# BT840_Temp.net
KiCad netlist of a schematic drawn in Altium Designer
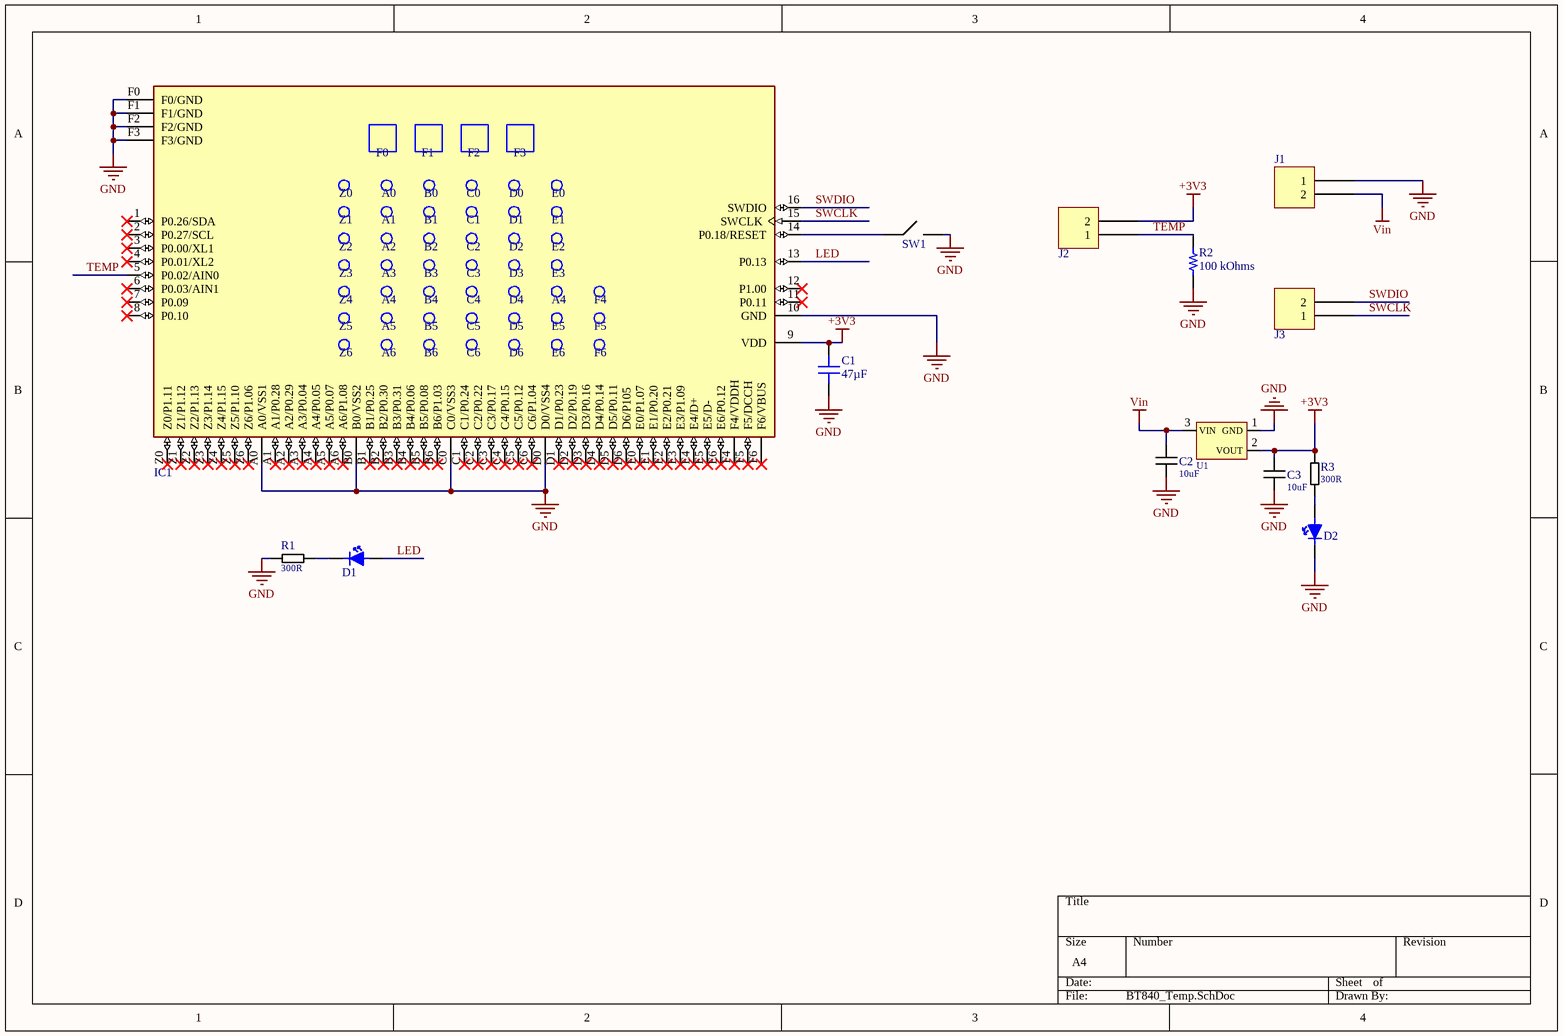
[diagram p0: BT840_Temp.SchDoc]

(export (version "E")
  (design (tool "Eeschema 10.0.6"))
  (components
    (comp (ref "C1")
      (value "47µF")
      (footprint "CAP 1206_3216 - 1.8MM")
      (description "CAP CER 47UF 6.3V X5R 1206")
      (fields (field (name "PART NUMBER") "12066D476MAT2A") (field (name "MANUFACTURER") "AVX Corporation"))
      (libsource (lib "Celestial Altium Library - altium_library") (part "Capacitor"))
    )
    (comp (ref "C2")
      (value "C1206C106J4RAC7800")
      (footprint "CAP_1206")
      (description "Cap Ceramic 10uF 16V ±%5 SMD 1206")
      (fields
        (field (name "MANUFACTURER") "KEMET")
        (field (name "MANUFACTURER PART NUMBER") "C1206C106J4RACTU")
        (field (name "CAPACITANCE") "10uF")
        (field (name "DESIGNED BY") "Semih AŞÇI")
      )
      (libsource (lib "Integrated_Library1") (part "CAP 10uF 1206"))
    )
    (comp (ref "C3")
      (value "C1206C106J4RAC7800")
      (footprint "CAP_1206")
      (description "Cap Ceramic 10uF 16V ±%5 SMD 1206")
      (fields
        (field (name "MANUFACTURER") "KEMET")
        (field (name "MANUFACTURER PART NUMBER") "C1206C106J4RACTU")
        (field (name "CAPACITANCE") "10uF")
        (field (name "DESIGNED BY") "Semih AŞÇI")
      )
      (libsource (lib "Integrated_Library1") (part "CAP 10uF 1206"))
    )
    (comp (ref "D1")
      (value "LED TH")
      (footprint "TH_LED")
      (description "Radial red led")
      (fields (field (name "DESIGNED BY") "Semih AŞÇI"))
      (libsource (lib "Integrated_Library1") (part "LED TH"))
    )
    (comp (ref "D2")
      (value "LED TH")
      (footprint "TH_LED")
      (description "Radial red led")
      (fields (field (name "DESIGNED BY") "Semih AŞÇI"))
      (libsource (lib "Integrated_Library1") (part "LED TH"))
    )
    (comp (ref "IC1")
      (value "BT480F")
      (footprint "BT840F")
      (description "BLE 5 Module: Nordic nRF52840 SoC (Range 930 Meters)")
      (fields
        (field (name "MANUFACTURER") "Fanstel")
        (field (name "MANUFACTURER PART NUMBER") "BT840F")
        (field (name "DESIGNED BY") "Semih AŞÇI")
      )
      (libsource (lib "Integrated_Library1") (part "BT840F"))
    )
    (comp (ref "J1")
      (value "B2B-PH-K-S(LF)(SN)")
      (footprint "JST B2B-PH-K")
      (description "CONN HEADER VERT 2POS 2MM")
      (fields (field (name "MANUFACTURER") "JST Sales America Inc."))
      (libsource (lib "") (part "2 Pin_1"))
    )
    (comp (ref "J2")
      (value "B2B-PH-K-S(LF)(SN)")
      (footprint "JST B2B-PH-K")
      (description "CONN HEADER VERT 2POS 2MM")
      (fields (field (name "MANUFACTURER") "JST Sales America Inc."))
      (libsource (lib "Celestial Altium Library - altium_library") (part "2 Pin"))
    )
    (comp (ref "J3")
      (value "B2B-PH-K-S(LF)(SN)")
      (footprint "JST B2B-PH-K")
      (description "CONN HEADER VERT 2POS 2MM")
      (fields (field (name "MANUFACTURER") "JST Sales America Inc."))
      (libsource (lib "Celestial Altium Library - altium_library") (part "2 Pin"))
    )
    (comp (ref "R1")
      (value "RT1206BRD07300RL")
      (footprint "RES_1206")
      (description "Res 300 Ohm %0.1   SMD 1206")
      (fields
        (field (name "MANUFACTURER") "Yageo")
        (field (name "TOLERANCE") "0.1%")
        (field (name "RESISTANCE") "300R")
        (field (name "DESIGNED BY") "Semih AŞÇI")
      )
      (libsource (lib "Integrated_Library1") (part "RES 300 OHM 1206"))
    )
    (comp (ref "R2")
      (value "100 kOhms")
      (footprint "RES 1206_3216")
      (description "RES 100K OHM 0.1% 1/8W 1206")
      (fields
        (field (name "PART NUMBER") "RNCS1206BKE100K")
        (field (name "MANUFACTURER") "Stackpole Electronics Inc")
      )
      (libsource (lib "Celestial Altium Library - altium_library") (part "Resistor"))
    )
    (comp (ref "R3")
      (value "RT1206BRD07300RL")
      (footprint "RES_1206")
      (description "Res 300 Ohm %0.1   SMD 1206")
      (fields
        (field (name "MANUFACTURER") "Yageo")
        (field (name "TOLERANCE") "0.1%")
        (field (name "RESISTANCE") "300R")
        (field (name "DESIGNED BY") "Semih AŞÇI")
      )
      (libsource (lib "Integrated_Library1") (part "RES 300 OHM 1206"))
    )
    (comp (ref "SW1")
      (value "PTS636 SM43J SMTR LFS")
      (footprint "SMD_Button")
      (description "PTS636 Series SPST-NO Off-Mom 180 gf Top Actuated J Lead SMT Tactile Switch")
      (fields
        (field (name "MANUFACTURER") "ITT C&K")
        (field (name "MANUFACTURER PART NUMBER") "PTS636SM43JSMTRLFS")
        (field (name "DESIGNED BY") "Semih AŞÇI")
      )
      (libsource (lib "Integrated_Library1") (part "SMD Button"))
    )
    (comp (ref "U1")
      (value "AMS1117-3.3V")
      (footprint "SOT223")
      (description "3.3V Voltage regulator")
      (fields
        (field (name "MANUFACTURER PART NUMBER") "AMS1117-3.3")
        (field (name "MANUFACTURER") "Advanced Monolithic Systems")
        (field (name "DESIGNED BY") "Semih AŞÇI")
      )
      (libsource (lib "Integrated_Library1") (part "AMS1117-3.3V SMD"))
    )
  )
  (nets
    (net (code "1") (name "+3V3") (class "Default")
      (node (ref "C1") (pin "2") (pinfunction "2_2") (pintype "passive"))
      (node (ref "C3") (pin "2") (pinfunction "2_2") (pintype "passive"))
      (node (ref "IC1") (pin "9") (pinfunction "VDD_9") (pintype "power_in"))
      (node (ref "J2") (pin "2") (pinfunction "2_2") (pintype "passive"))
      (node (ref "R3") (pin "2") (pinfunction "2_2") (pintype "passive"))
      (node (ref "U1") (pin "2") (pinfunction "VOUT_2") (pintype "passive"))
    )
    (net (code "2") (name "/LED") (class "Default")
      (node (ref "D1") (pin "2") (pinfunction "2_2") (pintype "passive"))
      (node (ref "IC1") (pin "13") (pinfunction "P0.13_13") (pintype "bidirectional"))
    )
    (net (code "3") (name "/SWCLK") (class "Default")
      (node (ref "IC1") (pin "15") (pinfunction "SWCLK_15") (pintype "input"))
      (node (ref "J3") (pin "1") (pinfunction "1_1") (pintype "passive"))
    )
    (net (code "4") (name "/SWDIO") (class "Default")
      (node (ref "IC1") (pin "16") (pinfunction "SWDIO_16") (pintype "bidirectional"))
      (node (ref "J3") (pin "2") (pinfunction "2_2") (pintype "passive"))
    )
    (net (code "5") (name "/TEMP") (class "Default")
      (node (ref "IC1") (pin "5") (pinfunction "P0.02/AIN0_5") (pintype "bidirectional"))
      (node (ref "J2") (pin "1") (pinfunction "1_1") (pintype "passive"))
      (node (ref "R2") (pin "2") (pinfunction "2_2") (pintype "passive"))
    )
    (net (code "6") (name "GND") (class "Default")
      (node (ref "C1") (pin "1") (pinfunction "1_1") (pintype "passive"))
      (node (ref "C2") (pin "1") (pinfunction "1_1") (pintype "passive"))
      (node (ref "C3") (pin "1") (pinfunction "1_1") (pintype "passive"))
      (node (ref "D2") (pin "1") (pinfunction "1_1") (pintype "passive"))
      (node (ref "IC1") (pin "10") (pinfunction "GND_10") (pintype "power_in"))
      (node (ref "IC1") (pin "A0") (pinfunction "A0/VSS1_A0") (pintype "power_in"))
      (node (ref "IC1") (pin "B0") (pinfunction "B0/VSS2_B0") (pintype "power_in"))
      (node (ref "IC1") (pin "C0") (pinfunction "C0/VSS3_C0") (pintype "power_in"))
      (node (ref "IC1") (pin "D0") (pinfunction "D0/VSS4_D0") (pintype "power_in"))
      (node (ref "IC1") (pin "F0") (pinfunction "F0/GND_F0") (pintype "power_in"))
      (node (ref "IC1") (pin "F1") (pinfunction "F1/GND_F1") (pintype "power_in"))
      (node (ref "IC1") (pin "F2") (pinfunction "F2/GND_F2") (pintype "power_in"))
      (node (ref "IC1") (pin "F3") (pinfunction "F3/GND_F3") (pintype "power_in"))
      (node (ref "J1") (pin "1") (pinfunction "1_1") (pintype "passive"))
      (node (ref "R1") (pin "1") (pinfunction "1_1") (pintype "passive"))
      (node (ref "R2") (pin "1") (pinfunction "1_1") (pintype "passive"))
      (node (ref "SW1") (pin "2") (pinfunction "2_2") (pintype "passive"))
      (node (ref "U1") (pin "1") (pinfunction "GND_1") (pintype "passive"))
    )
    (net (code "7") (name "Net-(D1-Pad1)") (class "Default")
      (node (ref "D1") (pin "1") (pinfunction "1_1") (pintype "passive"))
      (node (ref "R1") (pin "2") (pinfunction "2_2") (pintype "passive"))
    )
    (net (code "8") (name "Net-(D2-Pad2)") (class "Default")
      (node (ref "D2") (pin "2") (pinfunction "2_2") (pintype "passive"))
      (node (ref "R3") (pin "1") (pinfunction "1_1") (pintype "passive"))
    )
    (net (code "9") (name "Net-(IC1-P0.18{slash}RESET)") (class "Default")
      (node (ref "IC1") (pin "14") (pinfunction "P0.18/RESET_14") (pintype "bidirectional"))
      (node (ref "SW1") (pin "1") (pinfunction "1_1") (pintype "passive"))
    )
    (net (code "10") (name "Vin") (class "Default")
      (node (ref "C2") (pin "2") (pinfunction "2_2") (pintype "passive"))
      (node (ref "J1") (pin "2") (pinfunction "2_2") (pintype "passive"))
      (node (ref "U1") (pin "3") (pinfunction "VIN_3") (pintype "passive"))
    )
    (net (code "11") (name "unconnected-(IC1-A1{slash}P0.28-PadA1)") (class "Default")
      (node (ref "IC1") (pin "A1") (pinfunction "A1/P0.28_A1") (pintype "bidirectional+no_connect"))
    )
    (net (code "12") (name "unconnected-(IC1-A2{slash}P0.29-PadA2)") (class "Default")
      (node (ref "IC1") (pin "A2") (pinfunction "A2/P0.29_A2") (pintype "bidirectional+no_connect"))
    )
    (net (code "13") (name "unconnected-(IC1-A3{slash}P0.04-PadA3)") (class "Default")
      (node (ref "IC1") (pin "A3") (pinfunction "A3/P0.04_A3") (pintype "bidirectional+no_connect"))
    )
    (net (code "14") (name "unconnected-(IC1-A4{slash}P0.05-PadA4)") (class "Default")
      (node (ref "IC1") (pin "A4") (pinfunction "A4/P0.05_A4") (pintype "bidirectional+no_connect"))
    )
    (net (code "15") (name "unconnected-(IC1-A5{slash}P0.07-PadA5)") (class "Default")
      (node (ref "IC1") (pin "A5") (pinfunction "A5/P0.07_A5") (pintype "bidirectional+no_connect"))
    )
    (net (code "16") (name "unconnected-(IC1-A6{slash}P1.08-PadA6)") (class "Default")
      (node (ref "IC1") (pin "A6") (pinfunction "A6/P1.08_A6") (pintype "bidirectional+no_connect"))
    )
    (net (code "17") (name "unconnected-(IC1-B1{slash}P0.25-PadB1)") (class "Default")
      (node (ref "IC1") (pin "B1") (pinfunction "B1/P0.25_B1") (pintype "bidirectional+no_connect"))
    )
    (net (code "18") (name "unconnected-(IC1-B2{slash}P0.30-PadB2)") (class "Default")
      (node (ref "IC1") (pin "B2") (pinfunction "B2/P0.30_B2") (pintype "bidirectional+no_connect"))
    )
    (net (code "19") (name "unconnected-(IC1-B3{slash}P0.31-PadB3)") (class "Default")
      (node (ref "IC1") (pin "B3") (pinfunction "B3/P0.31_B3") (pintype "bidirectional+no_connect"))
    )
    (net (code "20") (name "unconnected-(IC1-B4{slash}P0.06-PadB4)") (class "Default")
      (node (ref "IC1") (pin "B4") (pinfunction "B4/P0.06_B4") (pintype "bidirectional+no_connect"))
    )
    (net (code "21") (name "unconnected-(IC1-B5{slash}P0.08-PadB5)") (class "Default")
      (node (ref "IC1") (pin "B5") (pinfunction "B5/P0.08_B5") (pintype "bidirectional+no_connect"))
    )
    (net (code "22") (name "unconnected-(IC1-B6{slash}P1.03-PadB6)") (class "Default")
      (node (ref "IC1") (pin "B6") (pinfunction "B6/P1.03_B6") (pintype "bidirectional+no_connect"))
    )
    (net (code "23") (name "unconnected-(IC1-C1{slash}P0.24-PadC1)") (class "Default")
      (node (ref "IC1") (pin "C1") (pinfunction "C1/P0.24_C1") (pintype "bidirectional+no_connect"))
    )
    (net (code "24") (name "unconnected-(IC1-C2{slash}P0.22-PadC2)") (class "Default")
      (node (ref "IC1") (pin "C2") (pinfunction "C2/P0.22_C2") (pintype "bidirectional+no_connect"))
    )
    (net (code "25") (name "unconnected-(IC1-C3{slash}P0.17-PadC3)") (class "Default")
      (node (ref "IC1") (pin "C3") (pinfunction "C3/P0.17_C3") (pintype "bidirectional+no_connect"))
    )
    (net (code "26") (name "unconnected-(IC1-C4{slash}P0.15-PadC4)") (class "Default")
      (node (ref "IC1") (pin "C4") (pinfunction "C4/P0.15_C4") (pintype "bidirectional+no_connect"))
    )
    (net (code "27") (name "unconnected-(IC1-C5{slash}P0.12-PadC5)") (class "Default")
      (node (ref "IC1") (pin "C5") (pinfunction "C5/P0.12_C5") (pintype "bidirectional+no_connect"))
    )
    (net (code "28") (name "unconnected-(IC1-C6{slash}P1.04-PadC6)") (class "Default")
      (node (ref "IC1") (pin "C6") (pinfunction "C6/P1.04_C6") (pintype "bidirectional+no_connect"))
    )
    (net (code "29") (name "unconnected-(IC1-D1{slash}P0.23-PadD1)") (class "Default")
      (node (ref "IC1") (pin "D1") (pinfunction "D1/P0.23_D1") (pintype "bidirectional+no_connect"))
    )
    (net (code "30") (name "unconnected-(IC1-D2{slash}P0.19-PadD2)") (class "Default")
      (node (ref "IC1") (pin "D2") (pinfunction "D2/P0.19_D2") (pintype "bidirectional+no_connect"))
    )
    (net (code "31") (name "unconnected-(IC1-D3{slash}P0.16-PadD3)") (class "Default")
      (node (ref "IC1") (pin "D3") (pinfunction "D3/P0.16_D3") (pintype "bidirectional+no_connect"))
    )
    (net (code "32") (name "unconnected-(IC1-D4{slash}P0.14-PadD4)") (class "Default")
      (node (ref "IC1") (pin "D4") (pinfunction "D4/P0.14_D4") (pintype "bidirectional+no_connect"))
    )
    (net (code "33") (name "unconnected-(IC1-D5{slash}P0.11-PadD5)") (class "Default")
      (node (ref "IC1") (pin "D5") (pinfunction "D5/P0.11_D5") (pintype "bidirectional+no_connect"))
    )
    (net (code "34") (name "unconnected-(IC1-D6{slash}P105-PadD6)") (class "Default")
      (node (ref "IC1") (pin "D6") (pinfunction "D6/P105_D6") (pintype "bidirectional+no_connect"))
    )
    (net (code "35") (name "unconnected-(IC1-E0{slash}P1.07-PadE0)") (class "Default")
      (node (ref "IC1") (pin "E0") (pinfunction "E0/P1.07_E0") (pintype "bidirectional+no_connect"))
    )
    (net (code "36") (name "unconnected-(IC1-E1{slash}P0.20-PadE1)") (class "Default")
      (node (ref "IC1") (pin "E1") (pinfunction "E1/P0.20_E1") (pintype "bidirectional+no_connect"))
    )
    (net (code "37") (name "unconnected-(IC1-E2{slash}P0.21-PadE2)") (class "Default")
      (node (ref "IC1") (pin "E2") (pinfunction "E2/P0.21_E2") (pintype "bidirectional+no_connect"))
    )
    (net (code "38") (name "unconnected-(IC1-E3{slash}P1.09-PadE3)") (class "Default")
      (node (ref "IC1") (pin "E3") (pinfunction "E3/P1.09_E3") (pintype "bidirectional+no_connect"))
    )
    (net (code "39") (name "unconnected-(IC1-E4{slash}D+-PadE4)") (class "Default")
      (node (ref "IC1") (pin "E4") (pinfunction "E4/D+_E4") (pintype "bidirectional+no_connect"))
    )
    (net (code "40") (name "unconnected-(IC1-E5{slash}D--PadE5)") (class "Default")
      (node (ref "IC1") (pin "E5") (pinfunction "E5/D-_E5") (pintype "bidirectional+no_connect"))
    )
    (net (code "41") (name "unconnected-(IC1-E6{slash}P0.12-PadE6)") (class "Default")
      (node (ref "IC1") (pin "E6") (pinfunction "E6/P0.12_E6") (pintype "bidirectional+no_connect"))
    )
    (net (code "42") (name "unconnected-(IC1-F4{slash}VDDH-PadF4)") (class "Default")
      (node (ref "IC1") (pin "F4") (pinfunction "F4/VDDH_F4") (pintype "power_in+no_connect"))
    )
    (net (code "43") (name "unconnected-(IC1-F5{slash}DCCH-PadF5)") (class "Default")
      (node (ref "IC1") (pin "F5") (pinfunction "F5/DCCH_F5") (pintype "bidirectional+no_connect"))
    )
    (net (code "44") (name "unconnected-(IC1-F6{slash}VBUS-PadF6)") (class "Default")
      (node (ref "IC1") (pin "F6") (pinfunction "F6/VBUS_F6") (pintype "power_in+no_connect"))
    )
    (net (code "45") (name "unconnected-(IC1-P0.00{slash}XL1-Pad3)") (class "Default")
      (node (ref "IC1") (pin "3") (pinfunction "P0.00/XL1_3") (pintype "bidirectional+no_connect"))
    )
    (net (code "46") (name "unconnected-(IC1-P0.01{slash}XL2-Pad4)") (class "Default")
      (node (ref "IC1") (pin "4") (pinfunction "P0.01/XL2_4") (pintype "bidirectional+no_connect"))
    )
    (net (code "47") (name "unconnected-(IC1-P0.03{slash}AIN1-Pad6)") (class "Default")
      (node (ref "IC1") (pin "6") (pinfunction "P0.03/AIN1_6") (pintype "bidirectional+no_connect"))
    )
    (net (code "48") (name "unconnected-(IC1-P0.09-Pad7)") (class "Default")
      (node (ref "IC1") (pin "7") (pinfunction "P0.09_7") (pintype "bidirectional+no_connect"))
    )
    (net (code "49") (name "unconnected-(IC1-P0.10-Pad8)") (class "Default")
      (node (ref "IC1") (pin "8") (pinfunction "P0.10_8") (pintype "bidirectional+no_connect"))
    )
    (net (code "50") (name "unconnected-(IC1-P0.11-Pad11)") (class "Default")
      (node (ref "IC1") (pin "11") (pinfunction "P0.11_11") (pintype "bidirectional+no_connect"))
    )
    (net (code "51") (name "unconnected-(IC1-P0.26{slash}SDA-Pad1)") (class "Default")
      (node (ref "IC1") (pin "1") (pinfunction "P0.26/SDA_1") (pintype "bidirectional+no_connect"))
    )
    (net (code "52") (name "unconnected-(IC1-P0.27{slash}SCL-Pad2)") (class "Default")
      (node (ref "IC1") (pin "2") (pinfunction "P0.27/SCL_2") (pintype "bidirectional+no_connect"))
    )
    (net (code "53") (name "unconnected-(IC1-P1.00-Pad12)") (class "Default")
      (node (ref "IC1") (pin "12") (pinfunction "P1.00_12") (pintype "bidirectional+no_connect"))
    )
    (net (code "54") (name "unconnected-(IC1-Z0{slash}P1.11-PadZ0)") (class "Default")
      (node (ref "IC1") (pin "Z0") (pinfunction "Z0/P1.11_Z0") (pintype "bidirectional+no_connect"))
    )
    (net (code "55") (name "unconnected-(IC1-Z1{slash}P1.12-PadZ1)") (class "Default")
      (node (ref "IC1") (pin "Z1") (pinfunction "Z1/P1.12_Z1") (pintype "bidirectional+no_connect"))
    )
    (net (code "56") (name "unconnected-(IC1-Z2{slash}P1.13-PadZ2)") (class "Default")
      (node (ref "IC1") (pin "Z2") (pinfunction "Z2/P1.13_Z2") (pintype "bidirectional+no_connect"))
    )
    (net (code "57") (name "unconnected-(IC1-Z3{slash}P1.14-PadZ3)") (class "Default")
      (node (ref "IC1") (pin "Z3") (pinfunction "Z3/P1.14_Z3") (pintype "bidirectional+no_connect"))
    )
    (net (code "58") (name "unconnected-(IC1-Z4{slash}P1.15-PadZ4)") (class "Default")
      (node (ref "IC1") (pin "Z4") (pinfunction "Z4/P1.15_Z4") (pintype "bidirectional+no_connect"))
    )
    (net (code "59") (name "unconnected-(IC1-Z5{slash}P1.10-PadZ5)") (class "Default")
      (node (ref "IC1") (pin "Z5") (pinfunction "Z5/P1.10_Z5") (pintype "bidirectional+no_connect"))
    )
    (net (code "60") (name "unconnected-(IC1-Z6{slash}P1.06-PadZ6)") (class "Default")
      (node (ref "IC1") (pin "Z6") (pinfunction "Z6/P1.06_Z6") (pintype "bidirectional+no_connect"))
    )
  )
)
